# 32a4u.net
KiCad netlist of a schematic drawn in EAGLE
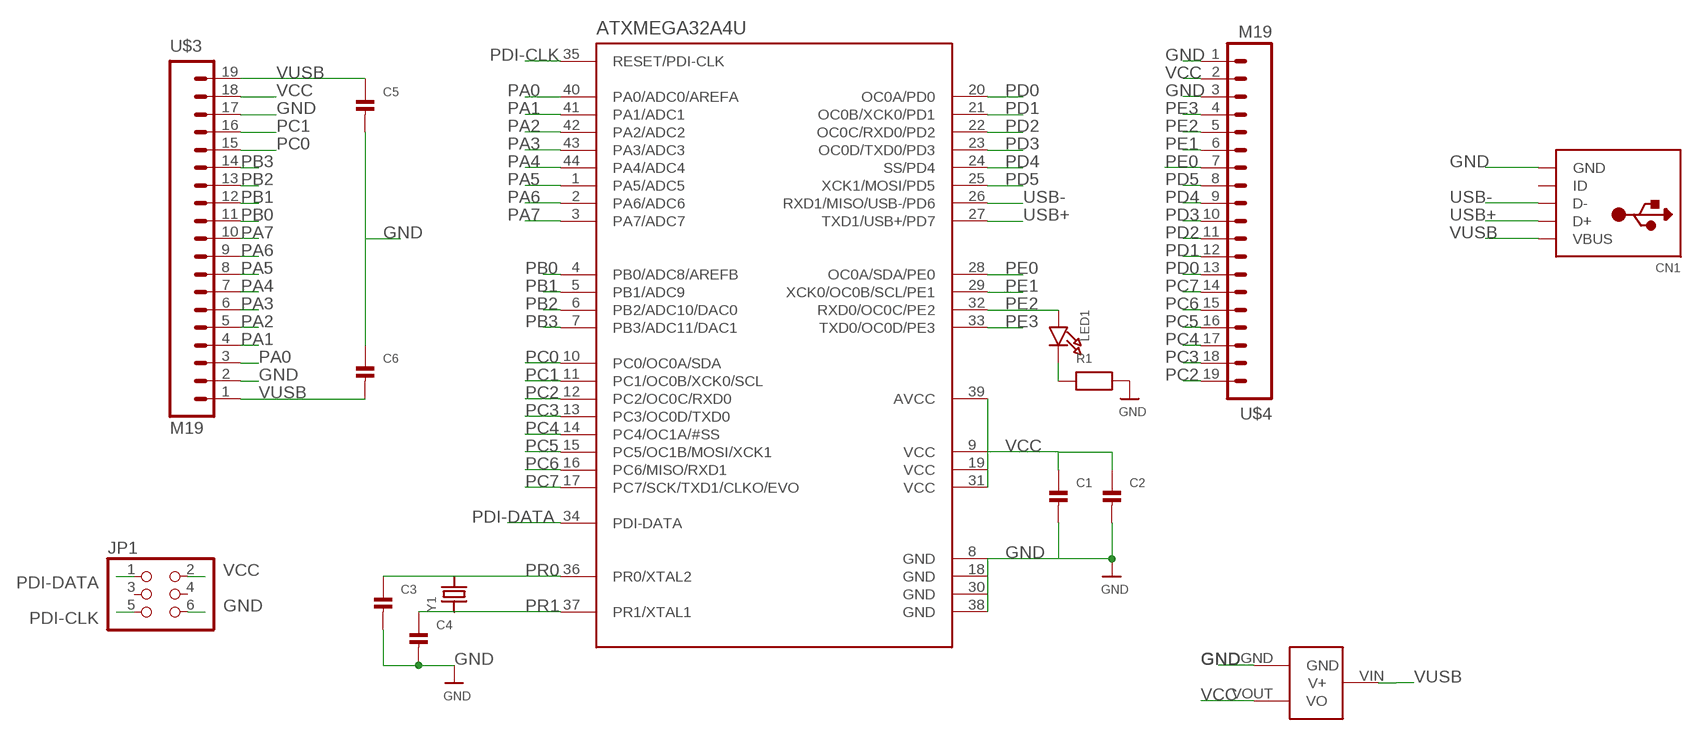
[diagram p0: schematic, sheet 1]

(export (version "E")
  (design (tool "Eeschema 10.0.6"))
  (components
    (comp (ref "ATXMEGA32A4U")
      (value "ATXMEGAXXA4U-AU")
      (footprint "eagle-import:TQFP-44")
      (libsource (lib "eagle-import") (part "ATXMEGAXXA4U-AU"))
    )
    (comp (ref "C1")
      (value "CAP_CERAMIC0603")
      (footprint "eagle-import:0603")
      (libsource (lib "eagle-import") (part "CAP_CERAMIC0603"))
    )
    (comp (ref "C2")
      (value "CAP_CERAMIC0603")
      (footprint "eagle-import:0603")
      (libsource (lib "eagle-import") (part "CAP_CERAMIC0603"))
    )
    (comp (ref "C3")
      (value "CAP_CERAMIC0603")
      (footprint "eagle-import:0603")
      (libsource (lib "eagle-import") (part "CAP_CERAMIC0603"))
    )
    (comp (ref "C4")
      (value "CAP_CERAMIC0603")
      (footprint "eagle-import:0603")
      (libsource (lib "eagle-import") (part "CAP_CERAMIC0603"))
    )
    (comp (ref "C5")
      (value "CAP_CERAMIC0603")
      (footprint "eagle-import:0603")
      (libsource (lib "eagle-import") (part "CAP_CERAMIC0603"))
    )
    (comp (ref "C6")
      (value "CAP_CERAMIC0603")
      (footprint "eagle-import:0603")
      (libsource (lib "eagle-import") (part "CAP_CERAMIC0603"))
    )
    (comp (ref "CN1")
      (value "USBMICROB")
      (footprint "eagle-import:USB-MICROB")
      (libsource (lib "eagle-import") (part "USBMICROB"))
    )
    (comp (ref "JP1")
      (value "HEADER-2X3")
      (footprint "eagle-import:2X03")
      (libsource (lib "eagle-import") (part "HEADER-2X3"))
    )
    (comp (ref "LED1")
      (value "LED0603")
      (footprint "eagle-import:CHIPLED_0603")
      (libsource (lib "eagle-import") (part "LED0603"))
    )
    (comp (ref "R1")
      (value "RESISTOR0603")
      (footprint "eagle-import:0603")
      (libsource (lib "eagle-import") (part "RESISTOR0603"))
    )
    (comp (ref "U$2")
      (value "MCP1700")
      (footprint "eagle-import:SOT23-3")
      (libsource (lib "eagle-import") (part "MCP1700"))
    )
    (comp (ref "U$3")
      (value "M19")
      (footprint "eagle-import:1X19")
      (libsource (lib "eagle-import") (part "M19"))
    )
    (comp (ref "U$4")
      (value "M19")
      (footprint "eagle-import:1X19")
      (libsource (lib "eagle-import") (part "M19"))
    )
    (comp (ref "Y1")
      (value "CRYSTAL")
      (footprint "eagle-import:NX8045GB")
      (libsource (lib "eagle-import") (part "CRYSTAL"))
    )
  )
  (nets
    (net (code "1") (name "/PA0") (class "Default")
      (node (ref "ATXMEGA32A4U") (pin "40") (pinfunction "PA0/ADC0/AREFA_40") (pintype "bidirectional"))
      (node (ref "U$3") (pin "3") (pinfunction "3_3") (pintype "passive"))
    )
    (net (code "2") (name "/PA1") (class "Default")
      (node (ref "ATXMEGA32A4U") (pin "41") (pinfunction "PA1/ADC1_41") (pintype "bidirectional"))
      (node (ref "U$3") (pin "4") (pinfunction "4_4") (pintype "passive"))
    )
    (net (code "3") (name "/PA2") (class "Default")
      (node (ref "ATXMEGA32A4U") (pin "42") (pinfunction "PA2/ADC2_42") (pintype "bidirectional"))
      (node (ref "U$3") (pin "5") (pinfunction "5_5") (pintype "passive"))
    )
    (net (code "4") (name "/PA3") (class "Default")
      (node (ref "ATXMEGA32A4U") (pin "43") (pinfunction "PA3/ADC3_43") (pintype "bidirectional"))
      (node (ref "U$3") (pin "6") (pinfunction "6_6") (pintype "passive"))
    )
    (net (code "5") (name "/PA4") (class "Default")
      (node (ref "ATXMEGA32A4U") (pin "44") (pinfunction "PA4/ADC4_44") (pintype "bidirectional"))
      (node (ref "U$3") (pin "7") (pinfunction "7_7") (pintype "passive"))
    )
    (net (code "6") (name "/PA5") (class "Default")
      (node (ref "ATXMEGA32A4U") (pin "1") (pinfunction "PA5/ADC5_1") (pintype "bidirectional"))
      (node (ref "U$3") (pin "8") (pinfunction "8_8") (pintype "passive"))
    )
    (net (code "7") (name "/PA6") (class "Default")
      (node (ref "ATXMEGA32A4U") (pin "2") (pinfunction "PA6/ADC6_2") (pintype "bidirectional"))
      (node (ref "U$3") (pin "9") (pinfunction "9_9") (pintype "passive"))
    )
    (net (code "8") (name "/PA7") (class "Default")
      (node (ref "ATXMEGA32A4U") (pin "3") (pinfunction "PA7/ADC7_3") (pintype "bidirectional"))
      (node (ref "U$3") (pin "10") (pinfunction "10_10") (pintype "passive"))
    )
    (net (code "9") (name "/PB0") (class "Default")
      (node (ref "ATXMEGA32A4U") (pin "4") (pinfunction "PB0/ADC8/AREFB_4") (pintype "bidirectional"))
      (node (ref "U$3") (pin "11") (pinfunction "11_11") (pintype "passive"))
    )
    (net (code "10") (name "/PB1") (class "Default")
      (node (ref "ATXMEGA32A4U") (pin "5") (pinfunction "PB1/ADC9_5") (pintype "bidirectional"))
      (node (ref "U$3") (pin "12") (pinfunction "12_12") (pintype "passive"))
    )
    (net (code "11") (name "/PB2") (class "Default")
      (node (ref "ATXMEGA32A4U") (pin "6") (pinfunction "PB2/ADC10/DAC0_6") (pintype "bidirectional"))
      (node (ref "U$3") (pin "13") (pinfunction "13_13") (pintype "passive"))
    )
    (net (code "12") (name "/PB3") (class "Default")
      (node (ref "ATXMEGA32A4U") (pin "7") (pinfunction "PB3/ADC11/DAC1_7") (pintype "bidirectional"))
      (node (ref "U$3") (pin "14") (pinfunction "14_14") (pintype "passive"))
    )
    (net (code "13") (name "/PC0") (class "Default")
      (node (ref "ATXMEGA32A4U") (pin "10") (pinfunction "PC0/OC0A/SDA_10") (pintype "bidirectional"))
      (node (ref "U$3") (pin "15") (pinfunction "15_15") (pintype "passive"))
    )
    (net (code "14") (name "/PC1") (class "Default")
      (node (ref "ATXMEGA32A4U") (pin "11") (pinfunction "PC1/OC0B/XCK0/SCL_11") (pintype "bidirectional"))
      (node (ref "U$3") (pin "16") (pinfunction "16_16") (pintype "passive"))
    )
    (net (code "15") (name "/PC2") (class "Default")
      (node (ref "ATXMEGA32A4U") (pin "12") (pinfunction "PC2/OC0C/RXD0_12") (pintype "bidirectional"))
      (node (ref "U$4") (pin "19") (pinfunction "19_19") (pintype "passive"))
    )
    (net (code "16") (name "/PC3") (class "Default")
      (node (ref "ATXMEGA32A4U") (pin "13") (pinfunction "PC3/OC0D/TXD0_13") (pintype "bidirectional"))
      (node (ref "U$4") (pin "18") (pinfunction "18_18") (pintype "passive"))
    )
    (net (code "17") (name "/PC4") (class "Default")
      (node (ref "ATXMEGA32A4U") (pin "14") (pinfunction "PC4/OC1A/#SS_14") (pintype "bidirectional"))
      (node (ref "U$4") (pin "17") (pinfunction "17_17") (pintype "passive"))
    )
    (net (code "18") (name "/PC5") (class "Default")
      (node (ref "ATXMEGA32A4U") (pin "15") (pinfunction "PC5/OC1B/MOSI/XCK1_15") (pintype "bidirectional"))
      (node (ref "U$4") (pin "16") (pinfunction "16_16") (pintype "passive"))
    )
    (net (code "19") (name "/PC6") (class "Default")
      (node (ref "ATXMEGA32A4U") (pin "16") (pinfunction "PC6/MISO/RXD1_16") (pintype "bidirectional"))
      (node (ref "U$4") (pin "15") (pinfunction "15_15") (pintype "passive"))
    )
    (net (code "20") (name "/PC7") (class "Default")
      (node (ref "ATXMEGA32A4U") (pin "17") (pinfunction "PC7/SCK/TXD1/CLKO/EVO_17") (pintype "bidirectional"))
      (node (ref "U$4") (pin "14") (pinfunction "14_14") (pintype "passive"))
    )
    (net (code "21") (name "/PD0") (class "Default")
      (node (ref "ATXMEGA32A4U") (pin "20") (pinfunction "OC0A/PD0_20") (pintype "bidirectional"))
      (node (ref "U$4") (pin "13") (pinfunction "13_13") (pintype "passive"))
    )
    (net (code "22") (name "/PD1") (class "Default")
      (node (ref "ATXMEGA32A4U") (pin "21") (pinfunction "OC0B/XCK0/PD1_21") (pintype "bidirectional"))
      (node (ref "U$4") (pin "12") (pinfunction "12_12") (pintype "passive"))
    )
    (net (code "23") (name "/PD2") (class "Default")
      (node (ref "ATXMEGA32A4U") (pin "22") (pinfunction "OC0C/RXD0/PD2_22") (pintype "bidirectional"))
      (node (ref "U$4") (pin "11") (pinfunction "11_11") (pintype "passive"))
    )
    (net (code "24") (name "/PD3") (class "Default")
      (node (ref "ATXMEGA32A4U") (pin "23") (pinfunction "OC0D/TXD0/PD3_23") (pintype "bidirectional"))
      (node (ref "U$4") (pin "10") (pinfunction "10_10") (pintype "passive"))
    )
    (net (code "25") (name "/PD4") (class "Default")
      (node (ref "ATXMEGA32A4U") (pin "24") (pinfunction "SS/PD4_24") (pintype "bidirectional"))
      (node (ref "U$4") (pin "9") (pinfunction "9_9") (pintype "passive"))
    )
    (net (code "26") (name "/PD5") (class "Default")
      (node (ref "ATXMEGA32A4U") (pin "25") (pinfunction "XCK1/MOSI/PD5_25") (pintype "bidirectional"))
      (node (ref "U$4") (pin "8") (pinfunction "8_8") (pintype "passive"))
    )
    (net (code "27") (name "/PDI-CLK") (class "Default")
      (node (ref "ATXMEGA32A4U") (pin "35") (pinfunction "RESET/PDI-CLK_35") (pintype "input"))
      (node (ref "JP1") (pin "5") (pinfunction "5_5") (pintype "passive"))
    )
    (net (code "28") (name "/PDI-DATA") (class "Default")
      (node (ref "ATXMEGA32A4U") (pin "34") (pinfunction "PDI-DATA_34") (pintype "bidirectional"))
      (node (ref "JP1") (pin "1") (pinfunction "1_1") (pintype "passive"))
    )
    (net (code "29") (name "/PE0") (class "Default")
      (node (ref "ATXMEGA32A4U") (pin "28") (pinfunction "OC0A/SDA/PE0_28") (pintype "bidirectional"))
      (node (ref "U$4") (pin "7") (pinfunction "7_7") (pintype "passive"))
    )
    (net (code "30") (name "/PE1") (class "Default")
      (node (ref "ATXMEGA32A4U") (pin "29") (pinfunction "XCK0/OC0B/SCL/PE1_29") (pintype "bidirectional"))
      (node (ref "U$4") (pin "6") (pinfunction "6_6") (pintype "passive"))
    )
    (net (code "31") (name "/PE2") (class "Default")
      (node (ref "ATXMEGA32A4U") (pin "32") (pinfunction "RXD0/OC0C/PE2_32") (pintype "bidirectional"))
      (node (ref "LED1") (pin "A") (pinfunction "A_A") (pintype "passive"))
      (node (ref "U$4") (pin "5") (pinfunction "5_5") (pintype "passive"))
    )
    (net (code "32") (name "/PE3") (class "Default")
      (node (ref "ATXMEGA32A4U") (pin "33") (pinfunction "TXD0/OC0D/PE3_33") (pintype "bidirectional"))
      (node (ref "U$4") (pin "4") (pinfunction "4_4") (pintype "passive"))
    )
    (net (code "33") (name "/PR0") (class "Default")
      (node (ref "ATXMEGA32A4U") (pin "36") (pinfunction "PR0/XTAL2_36") (pintype "bidirectional"))
      (node (ref "C3") (pin "1") (pinfunction "P$1_1") (pintype "passive"))
      (node (ref "Y1") (pin "P$2") (pinfunction "2_P$2") (pintype "passive"))
    )
    (net (code "34") (name "/PR1") (class "Default")
      (node (ref "ATXMEGA32A4U") (pin "37") (pinfunction "PR1/XTAL1_37") (pintype "bidirectional"))
      (node (ref "C4") (pin "1") (pinfunction "P$1_1") (pintype "passive"))
      (node (ref "Y1") (pin "P$1") (pinfunction "1_P$1") (pintype "passive"))
    )
    (net (code "35") (name "/USB+") (class "Default")
      (node (ref "ATXMEGA32A4U") (pin "27") (pinfunction "TXD1/USB+/PD7_27") (pintype "bidirectional"))
      (node (ref "CN1") (pin "P3") (pinfunction "D+_P3") (pintype "bidirectional"))
    )
    (net (code "36") (name "/USB-") (class "Default")
      (node (ref "ATXMEGA32A4U") (pin "26") (pinfunction "RXD1/MISO/USB-/PD6_26") (pintype "bidirectional"))
      (node (ref "CN1") (pin "P2") (pinfunction "D-_P2") (pintype "bidirectional"))
    )
    (net (code "37") (name "/VCC") (class "Default")
      (node (ref "ATXMEGA32A4U") (pin "19") (pinfunction "VCC_19") (pintype "power_in"))
      (node (ref "ATXMEGA32A4U") (pin "31") (pinfunction "VCC_31") (pintype "power_in"))
      (node (ref "ATXMEGA32A4U") (pin "39") (pinfunction "AVCC_39") (pintype "power_in"))
      (node (ref "ATXMEGA32A4U") (pin "9") (pinfunction "VCC_9") (pintype "power_in"))
      (node (ref "C1") (pin "1") (pinfunction "P$1_1") (pintype "passive"))
      (node (ref "C2") (pin "1") (pinfunction "P$1_1") (pintype "passive"))
      (node (ref "JP1") (pin "2") (pinfunction "2_2") (pintype "passive"))
      (node (ref "U$2") (pin "VOUT") (pinfunction "VO_VOUT") (pintype "bidirectional"))
      (node (ref "U$3") (pin "18") (pinfunction "18_18") (pintype "passive"))
      (node (ref "U$4") (pin "2") (pinfunction "2_2") (pintype "passive"))
    )
    (net (code "38") (name "/VUSB") (class "Default")
      (node (ref "C5") (pin "1") (pinfunction "P$1_1") (pintype "passive"))
      (node (ref "C6") (pin "2") (pinfunction "P$2_2") (pintype "passive"))
      (node (ref "CN1") (pin "P1") (pinfunction "VBUS_P1") (pintype "power_in"))
      (node (ref "U$2") (pin "VIN") (pinfunction "V+_VIN") (pintype "bidirectional"))
      (node (ref "U$3") (pin "1") (pinfunction "1_1") (pintype "passive"))
      (node (ref "U$3") (pin "19") (pinfunction "19_19") (pintype "passive"))
    )
    (net (code "39") (name "GND") (class "Default")
      (node (ref "ATXMEGA32A4U") (pin "18") (pinfunction "GND_18") (pintype "power_in"))
      (node (ref "ATXMEGA32A4U") (pin "30") (pinfunction "GND_30") (pintype "power_in"))
      (node (ref "ATXMEGA32A4U") (pin "38") (pinfunction "GND_38") (pintype "power_in"))
      (node (ref "ATXMEGA32A4U") (pin "8") (pinfunction "GND_8") (pintype "power_in"))
      (node (ref "C1") (pin "2") (pinfunction "P$2_2") (pintype "passive"))
      (node (ref "C2") (pin "2") (pinfunction "P$2_2") (pintype "passive"))
      (node (ref "C3") (pin "2") (pinfunction "P$2_2") (pintype "passive"))
      (node (ref "C4") (pin "2") (pinfunction "P$2_2") (pintype "passive"))
      (node (ref "C5") (pin "2") (pinfunction "P$2_2") (pintype "passive"))
      (node (ref "C6") (pin "1") (pinfunction "P$1_1") (pintype "passive"))
      (node (ref "CN1") (pin "P5") (pinfunction "GND_P5") (pintype "power_in"))
      (node (ref "JP1") (pin "6") (pinfunction "6_6") (pintype "passive"))
      (node (ref "R1") (pin "2") (pinfunction "2_2") (pintype "passive"))
      (node (ref "U$2") (pin "GND") (pinfunction "GND_GND") (pintype "bidirectional"))
      (node (ref "U$3") (pin "17") (pinfunction "17_17") (pintype "passive"))
      (node (ref "U$3") (pin "2") (pinfunction "2_2") (pintype "passive"))
      (node (ref "U$4") (pin "1") (pinfunction "1_1") (pintype "passive"))
      (node (ref "U$4") (pin "3") (pinfunction "3_3") (pintype "passive"))
    )
    (net (code "40") (name "Net-(LED1-PadC)") (class "Default")
      (node (ref "LED1") (pin "C") (pinfunction "C_C") (pintype "passive"))
      (node (ref "R1") (pin "1") (pinfunction "1_1") (pintype "passive"))
    )
    (net (code "41") (name "unconnected-(CN1-ID-PadP4)") (class "Default")
      (node (ref "CN1") (pin "P4") (pinfunction "ID_P4") (pintype "bidirectional"))
    )
    (net (code "42") (name "unconnected-(JP1-Pad3)") (class "Default")
      (node (ref "JP1") (pin "3") (pinfunction "3_3") (pintype "passive"))
    )
    (net (code "43") (name "unconnected-(JP1-Pad4)") (class "Default")
      (node (ref "JP1") (pin "4") (pinfunction "4_4") (pintype "passive"))
    )
  )
)
